# PowerDrivers.net
KiCad netlist of a schematic drawn in Altium Designer
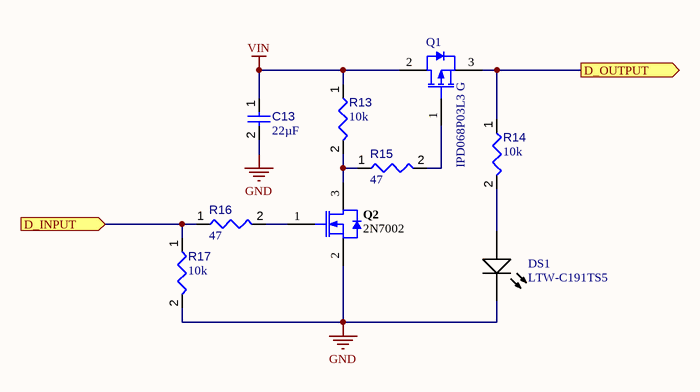
[diagram p0: PowerDrivers.SchDoc]

(export (version "E")
  (design (tool "Eeschema 10.0.6"))
  (components
    (comp (ref "C13")
      (value "22µF")
      (footprint "CAPC0805(2012)145_L")
      (description "Chip Capacitor, 22µF +/-40%, 16V, 0805, Thickness 1.45 mm")
      (fields (field (name "TOLERANCE") "5%") (field (name "Comment") "Capacitor 22µF +/-40% 16V 0805"))
      (libsource (lib "UdeA") (part "CAP-NP-2"))
    )
    (comp (ref "DS1")
      (value "LTW-C191TS5")
      (footprint "LTST-LTW-C191TS5_V")
      (description "LED Uni-Color White, 70 mW, 20 mA, -20 to 80 degC, 2-Pin SMD, RoHS, Tape and Reel")
      (fields (field (name "POWER") "70mW") (field (name "MANUFACTURER") "Lite-On"))
      (libsource (lib "UdeA") (part "LED-WHITE-AK-2"))
    )
    (comp (ref "Q1")
      (value "IPD068P03L3 G")
      (footprint "INF-PG-TO252-3-1_L")
      (fields (field (name "MANUFACTURER") "Infineon"))
      (libsource (lib "Altium Content Vault") (part "INF-PEMOS-GDS-3"))
    )
    (comp (ref "Q2")
      (value "2N7002")
      (footprint "INF-PG-SOT23_M")
      (fields (field (name "MANUFACTURER") "Infineon"))
      (libsource (lib "Altium Content Vault") (part "INF-NDMOS-GSD-3"))
    )
    (comp (ref "R13")
      (value "10k")
      (footprint "RESC1608X55X25ML10T15")
      (description "Chip Resistor, 10 KOhm, +/- 1%, 01 W, -55 to 155 degC, 0603 (1608 Metric)")
      (fields (field (name "POWER") "100mW") (field (name "TOLERANCE") "1%"))
      (libsource (lib "UdeA") (part "RES-2"))
    )
    (comp (ref "R14")
      (value "10k")
      (footprint "RESC1608X55X25ML10T15")
      (description "Chip Resistor, 10 KOhm, +/- 1%, 01 W, -55 to 155 degC, 0603 (1608 Metric)")
      (fields (field (name "POWER") "100mW") (field (name "TOLERANCE") "1%"))
      (libsource (lib "UdeA") (part "RES-2"))
    )
    (comp (ref "R15")
      (value "47")
      (footprint "RESC1608X55X25ML10T15")
      (description "Chip Resistor, 10 KOhm, +/- 1%, 01 W, -55 to 155 degC, 0603 (1608 Metric)")
      (fields (field (name "POWER") "100mW") (field (name "TOLERANCE") "1%"))
      (libsource (lib "UdeA") (part "RES-2"))
    )
    (comp (ref "R16")
      (value "47")
      (footprint "RESC1608X55X25ML10T15")
      (description "Chip Resistor, 10 KOhm, +/- 1%, 01 W, -55 to 155 degC, 0603 (1608 Metric)")
      (fields (field (name "POWER") "100mW") (field (name "TOLERANCE") "1%"))
      (libsource (lib "UdeA") (part "RES-2"))
    )
    (comp (ref "R17")
      (value "10k")
      (footprint "RESC1608X55X25ML10T15")
      (description "Chip Resistor, 10 KOhm, +/- 1%, 01 W, -55 to 155 degC, 0603 (1608 Metric)")
      (fields (field (name "POWER") "100mW") (field (name "TOLERANCE") "1%"))
      (libsource (lib "UdeA") (part "RES-2"))
    )
  )
  (nets
    (net (code "1") (name "/D_INPUT") (class "Default")
      (node (ref "R16") (pin "1") (pinfunction "1_1") (pintype "passive"))
      (node (ref "R17") (pin "1") (pinfunction "1_1") (pintype "passive"))
    )
    (net (code "2") (name "/D_OUTPUT") (class "Default")
      (node (ref "Q1") (pin "3") (pinfunction "SOURCE_3") (pintype "passive"))
      (node (ref "R14") (pin "1") (pinfunction "1_1") (pintype "passive"))
    )
    (net (code "3") (name "GND") (class "Default")
      (node (ref "C13") (pin "2") (pinfunction "2_2") (pintype "passive"))
      (node (ref "DS1") (pin "2") (pinfunction "K_2") (pintype "passive"))
      (node (ref "Q2") (pin "2") (pinfunction "SOURCE_2") (pintype "passive"))
      (node (ref "R17") (pin "2") (pinfunction "2_2") (pintype "passive"))
    )
    (net (code "4") (name "Net-(DS1-A)") (class "Default")
      (node (ref "DS1") (pin "1") (pinfunction "A_1") (pintype "passive"))
      (node (ref "R14") (pin "2") (pinfunction "2_2") (pintype "passive"))
    )
    (net (code "5") (name "Net-(Q1-GATE)") (class "Default")
      (node (ref "Q1") (pin "1") (pinfunction "GATE_1") (pintype "passive"))
      (node (ref "R15") (pin "2") (pinfunction "2_2") (pintype "passive"))
    )
    (net (code "6") (name "Net-(Q2-DRAIN)") (class "Default")
      (node (ref "Q2") (pin "3") (pinfunction "DRAIN_3") (pintype "passive"))
      (node (ref "R13") (pin "2") (pinfunction "2_2") (pintype "passive"))
      (node (ref "R15") (pin "1") (pinfunction "1_1") (pintype "passive"))
    )
    (net (code "7") (name "Net-(Q2-GATE)") (class "Default")
      (node (ref "Q2") (pin "1") (pinfunction "GATE_1") (pintype "passive"))
      (node (ref "R16") (pin "2") (pinfunction "2_2") (pintype "passive"))
    )
    (net (code "8") (name "VIN") (class "Default")
      (node (ref "C13") (pin "1") (pinfunction "1_1") (pintype "passive"))
      (node (ref "Q1") (pin "2") (pinfunction "DRAIN_2") (pintype "passive"))
      (node (ref "R13") (pin "1") (pinfunction "1_1") (pintype "passive"))
    )
  )
)
